# SCH.net
KiCad netlist of a schematic drawn in EasyEDA
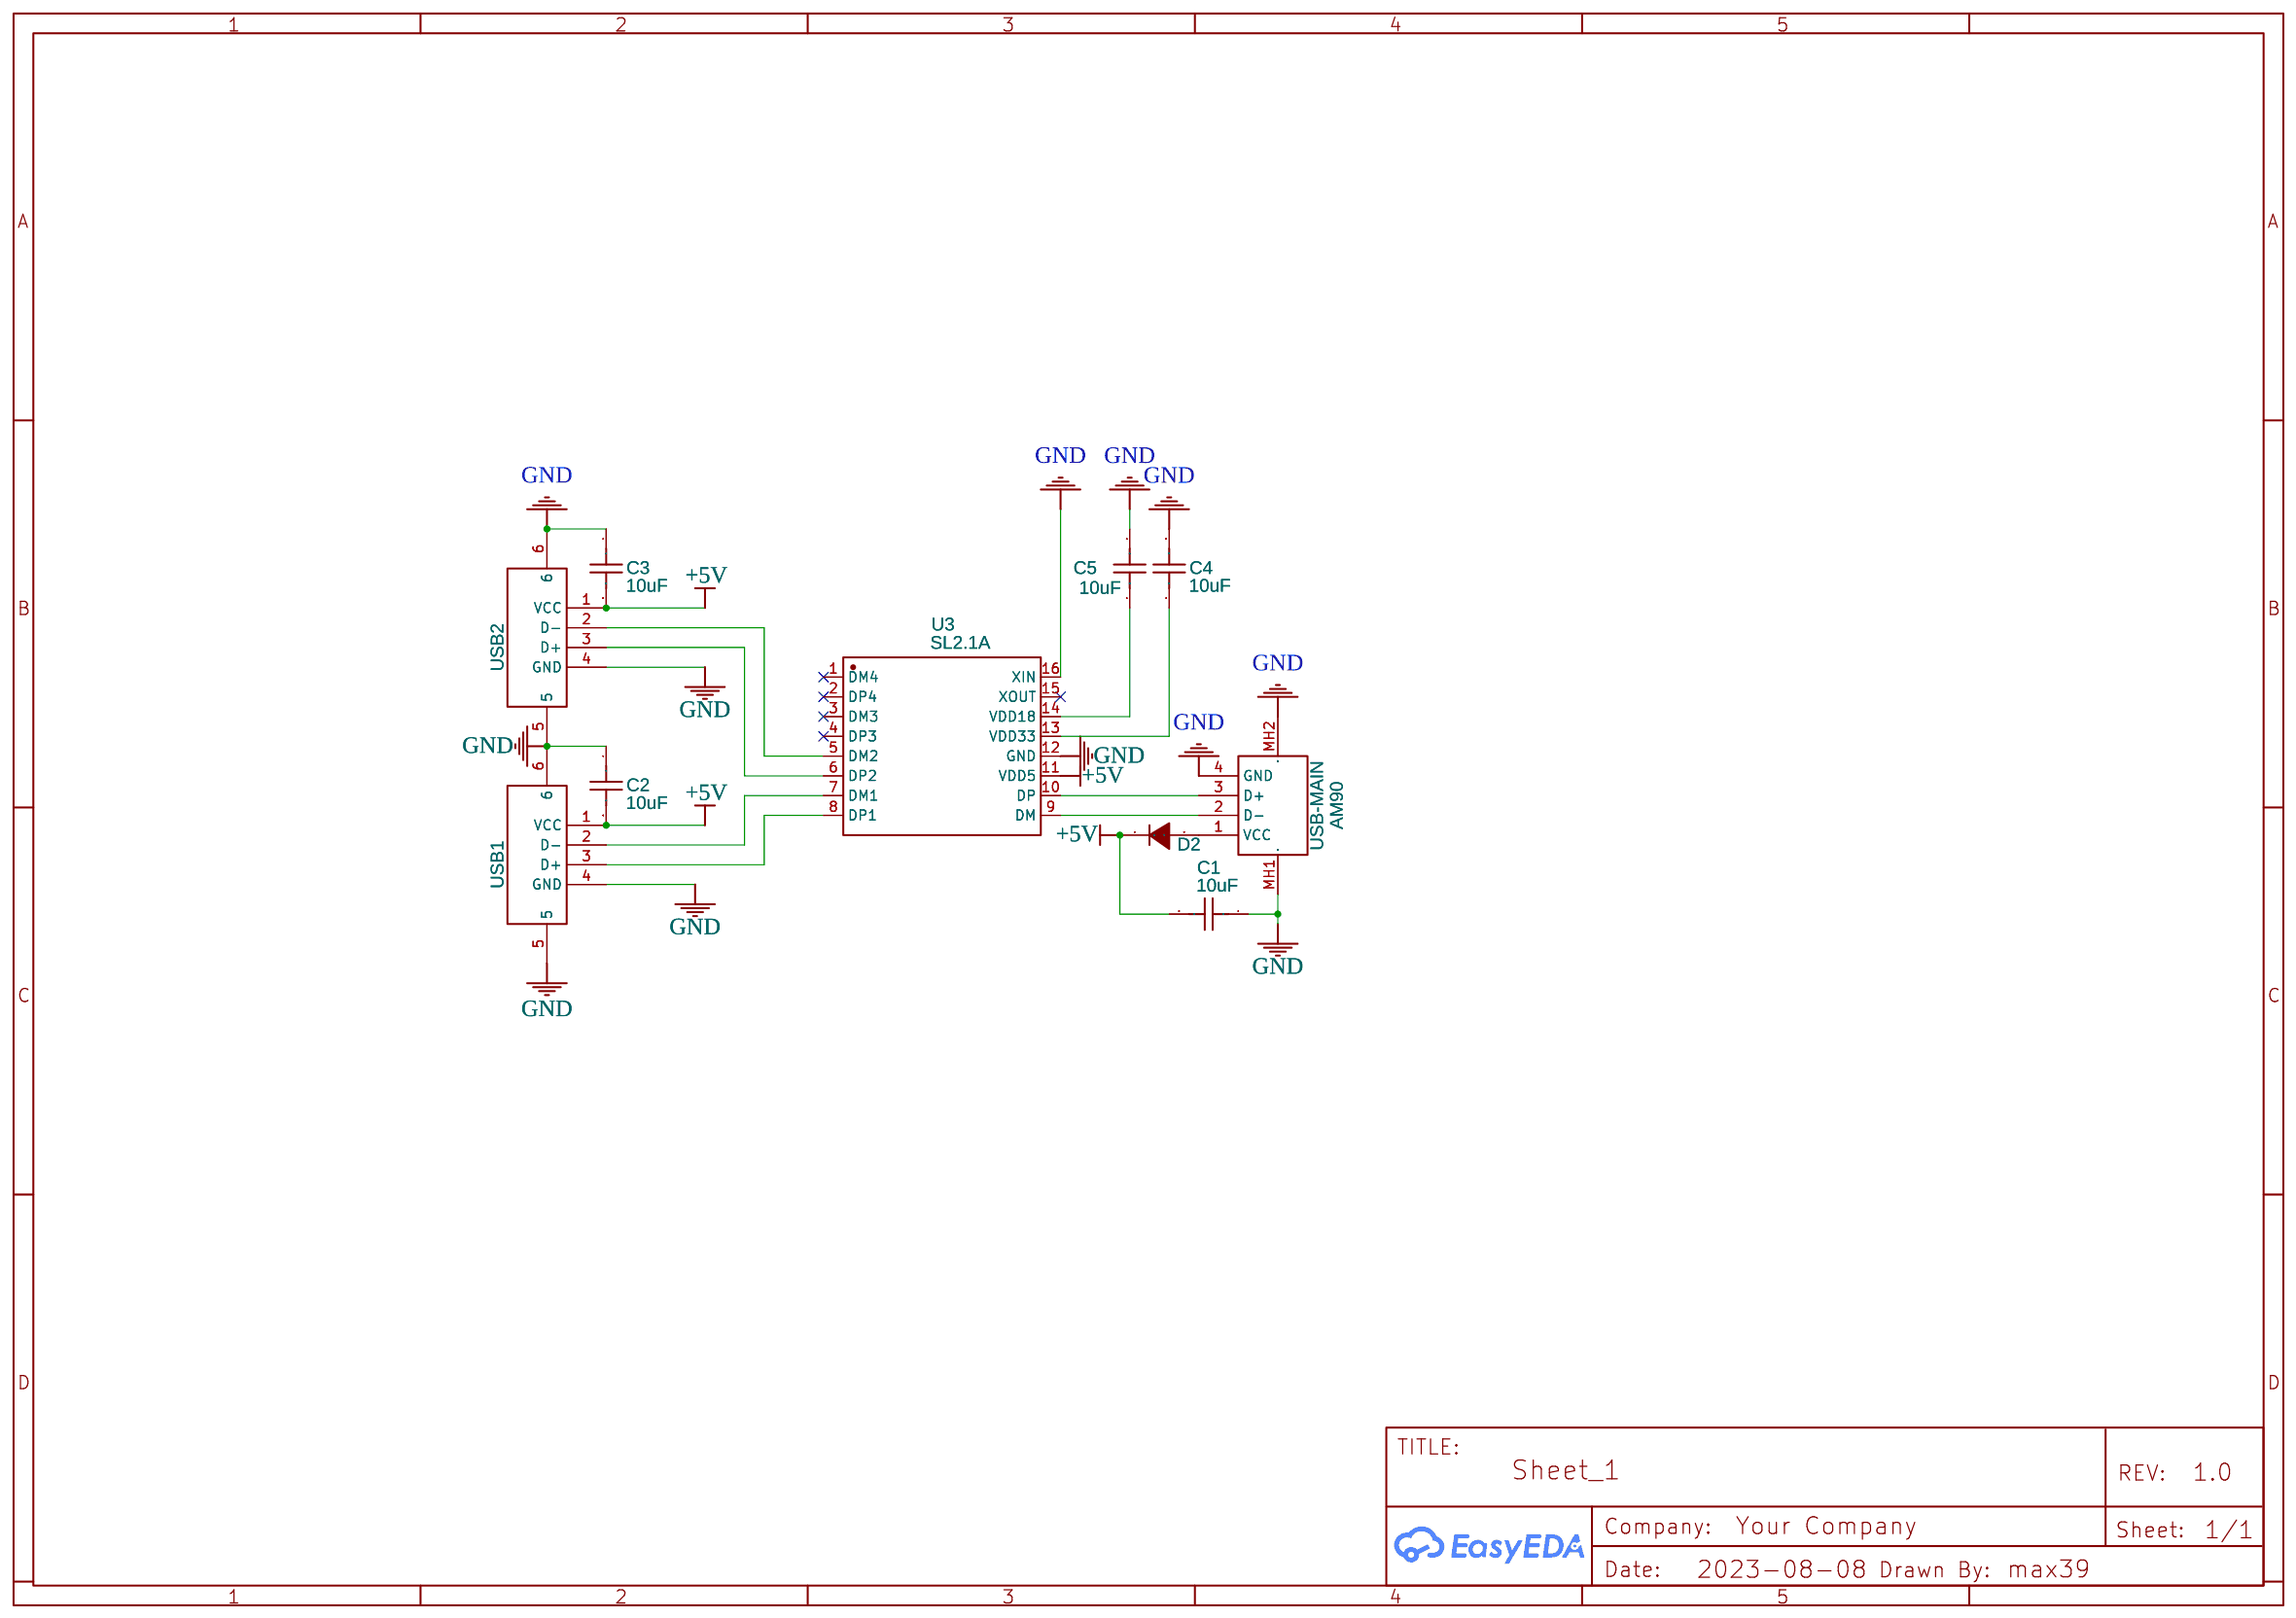
[diagram p0: schematic sheet]

(export (version "E")
  (design (tool "Eeschema 10.0.6"))
  (components
    (comp (ref "C1")
      (value "10uF")
      (fields
        (field (name "Manufacturer Part") "CL10A106KP8NNNC")
        (field (name "Manufacturer") "SAMSUNG(三星)")
      )
      (libsource (lib "") (part "CL10A106KP8NNNC_1"))
    )
    (comp (ref "C2")
      (value "10uF")
      (fields
        (field (name "Manufacturer Part") "CL10A106KP8NNNC")
        (field (name "Manufacturer") "SAMSUNG(三星)")
      )
      (libsource (lib "") (part "CL10A106KP8NNNC"))
    )
    (comp (ref "C3")
      (value "10uF")
      (fields
        (field (name "Manufacturer Part") "CL10A106KP8NNNC")
        (field (name "Manufacturer") "SAMSUNG(三星)")
      )
      (libsource (lib "") (part "CL10A106KP8NNNC"))
    )
    (comp (ref "C4") (value "10uF") (libsource (lib "") (part "C_0603_US")))
    (comp (ref "C5") (value "10uF") (libsource (lib "") (part "C_0603_US")))
    (comp (ref "D2")
      (value "NSR0320MW2T1G")
      (fields (field (name "Manufacturer") "onsemi(安森美)"))
      (libsource (lib "") (part "NSR0320MW2T1G"))
    )
    (comp (ref "U3")
      (value "SL2.1A")
      (fields (field (name "Manufacturer") "CoreChips(和芯润德)"))
      (libsource (lib "") (part "SL2.1A"))
    )
    (comp (ref "USB-MAIN") (value "AM90") (libsource (lib "") (part "AM90")))
    (comp (ref "USB1")
      (value "USB-AF-90-14.4X13.6-H7.0-DIP")
      (fields (field (name "Manufacturer Part") "903-131A1011D10100") (field (name "Manufacturer") "精拓金"))
      (libsource (lib "") (part "USB-AF-90-14.4X13.6-H7.0-DIP"))
    )
    (comp (ref "USB2")
      (value "USB-AF-90-14.4X13.6-H7.0-DIP")
      (fields (field (name "Manufacturer Part") "903-131A1011D10100") (field (name "Manufacturer") "精拓金"))
      (libsource (lib "") (part "USB-AF-90-14.4X13.6-H7.0-DIP"))
    )
  )
  (nets
    (net (code "1") (name "+5V") (class "Default")
      (node (ref "C1") (pin "2") (pinfunction "2_2") (pintype "unspecified"))
      (node (ref "C2") (pin "2") (pinfunction "2_2") (pintype "unspecified"))
      (node (ref "C3") (pin "2") (pinfunction "2_2") (pintype "unspecified"))
      (node (ref "D2") (pin "1") (pinfunction "C_1") (pintype "unspecified"))
      (node (ref "U3") (pin "11") (pinfunction "VDD5_11") (pintype "unspecified"))
      (node (ref "USB1") (pin "1") (pinfunction "VCC_1") (pintype "unspecified"))
      (node (ref "USB2") (pin "1") (pinfunction "VCC_1") (pintype "unspecified"))
    )
    (net (code "2") (name "GND") (class "Default")
      (node (ref "C1") (pin "1") (pinfunction "1_1") (pintype "unspecified"))
      (node (ref "C2") (pin "1") (pinfunction "1_1") (pintype "unspecified"))
      (node (ref "C3") (pin "1") (pinfunction "1_1") (pintype "unspecified"))
      (node (ref "C4") (pin "2") (pinfunction "2_2") (pintype "unspecified"))
      (node (ref "C5") (pin "2") (pinfunction "2_2") (pintype "unspecified"))
      (node (ref "U3") (pin "12") (pinfunction "GND_12") (pintype "unspecified"))
      (node (ref "U3") (pin "16") (pinfunction "XIN_16") (pintype "unspecified"))
      (node (ref "USB-MAIN") (pin "4") (pinfunction "GND_4") (pintype "input"))
      (node (ref "USB-MAIN") (pin "MH1") (pinfunction "MH1_MH1") (pintype "unspecified"))
      (node (ref "USB-MAIN") (pin "MH2") (pinfunction "MH2_MH2") (pintype "unspecified"))
      (node (ref "USB1") (pin "4") (pinfunction "GND_4") (pintype "unspecified"))
      (node (ref "USB1") (pin "5") (pinfunction "5_5") (pintype "unspecified"))
      (node (ref "USB1") (pin "6") (pinfunction "6_6") (pintype "unspecified"))
      (node (ref "USB2") (pin "4") (pinfunction "GND_4") (pintype "unspecified"))
      (node (ref "USB2") (pin "5") (pinfunction "5_5") (pintype "unspecified"))
      (node (ref "USB2") (pin "6") (pinfunction "6_6") (pintype "unspecified"))
    )
    (net (code "3") (name "Net-(D2-A)") (class "Default")
      (node (ref "D2") (pin "2") (pinfunction "A_2") (pintype "unspecified"))
      (node (ref "USB-MAIN") (pin "1") (pinfunction "VCC_1") (pintype "input"))
    )
    (net (code "4") (name "Net-(U3-DM)") (class "Default")
      (node (ref "U3") (pin "9") (pinfunction "DM_9") (pintype "unspecified"))
      (node (ref "USB-MAIN") (pin "2") (pinfunction "D-_2") (pintype "input"))
    )
    (net (code "5") (name "Net-(U3-DM1)") (class "Default")
      (node (ref "U3") (pin "7") (pinfunction "DM1_7") (pintype "unspecified"))
      (node (ref "USB1") (pin "2") (pinfunction "D-_2") (pintype "unspecified"))
    )
    (net (code "6") (name "Net-(U3-DM2)") (class "Default")
      (node (ref "U3") (pin "5") (pinfunction "DM2_5") (pintype "unspecified"))
      (node (ref "USB2") (pin "2") (pinfunction "D-_2") (pintype "unspecified"))
    )
    (net (code "7") (name "Net-(U3-DP)") (class "Default")
      (node (ref "U3") (pin "10") (pinfunction "DP_10") (pintype "unspecified"))
      (node (ref "USB-MAIN") (pin "3") (pinfunction "D+_3") (pintype "input"))
    )
    (net (code "8") (name "Net-(U3-DP1)") (class "Default")
      (node (ref "U3") (pin "8") (pinfunction "DP1_8") (pintype "unspecified"))
      (node (ref "USB1") (pin "3") (pinfunction "D+_3") (pintype "unspecified"))
    )
    (net (code "9") (name "Net-(U3-DP2)") (class "Default")
      (node (ref "U3") (pin "6") (pinfunction "DP2_6") (pintype "unspecified"))
      (node (ref "USB2") (pin "3") (pinfunction "D+_3") (pintype "unspecified"))
    )
    (net (code "10") (name "Net-(U3-VDD18)") (class "Default")
      (node (ref "C5") (pin "1") (pinfunction "1_1") (pintype "unspecified"))
      (node (ref "U3") (pin "14") (pinfunction "VDD18_14") (pintype "unspecified"))
    )
    (net (code "11") (name "Net-(U3-VDD33)") (class "Default")
      (node (ref "C4") (pin "1") (pinfunction "1_1") (pintype "unspecified"))
      (node (ref "U3") (pin "13") (pinfunction "VDD33_13") (pintype "unspecified"))
    )
    (net (code "12") (name "unconnected-(U3-DM3-Pad3)") (class "Default")
      (node (ref "U3") (pin "3") (pinfunction "DM3_3") (pintype "unspecified+no_connect"))
    )
    (net (code "13") (name "unconnected-(U3-DM4-Pad1)") (class "Default")
      (node (ref "U3") (pin "1") (pinfunction "DM4_1") (pintype "unspecified+no_connect"))
    )
    (net (code "14") (name "unconnected-(U3-DP3-Pad4)") (class "Default")
      (node (ref "U3") (pin "4") (pinfunction "DP3_4") (pintype "unspecified+no_connect"))
    )
    (net (code "15") (name "unconnected-(U3-DP4-Pad2)") (class "Default")
      (node (ref "U3") (pin "2") (pinfunction "DP4_2") (pintype "unspecified+no_connect"))
    )
    (net (code "16") (name "unconnected-(U3-XOUT-Pad15)") (class "Default")
      (node (ref "U3") (pin "15") (pinfunction "XOUT_15") (pintype "unspecified+no_connect"))
    )
  )
)
